# CW308T_PSoC62_MCU.net
KiCad netlist of a schematic drawn in Altium Designer
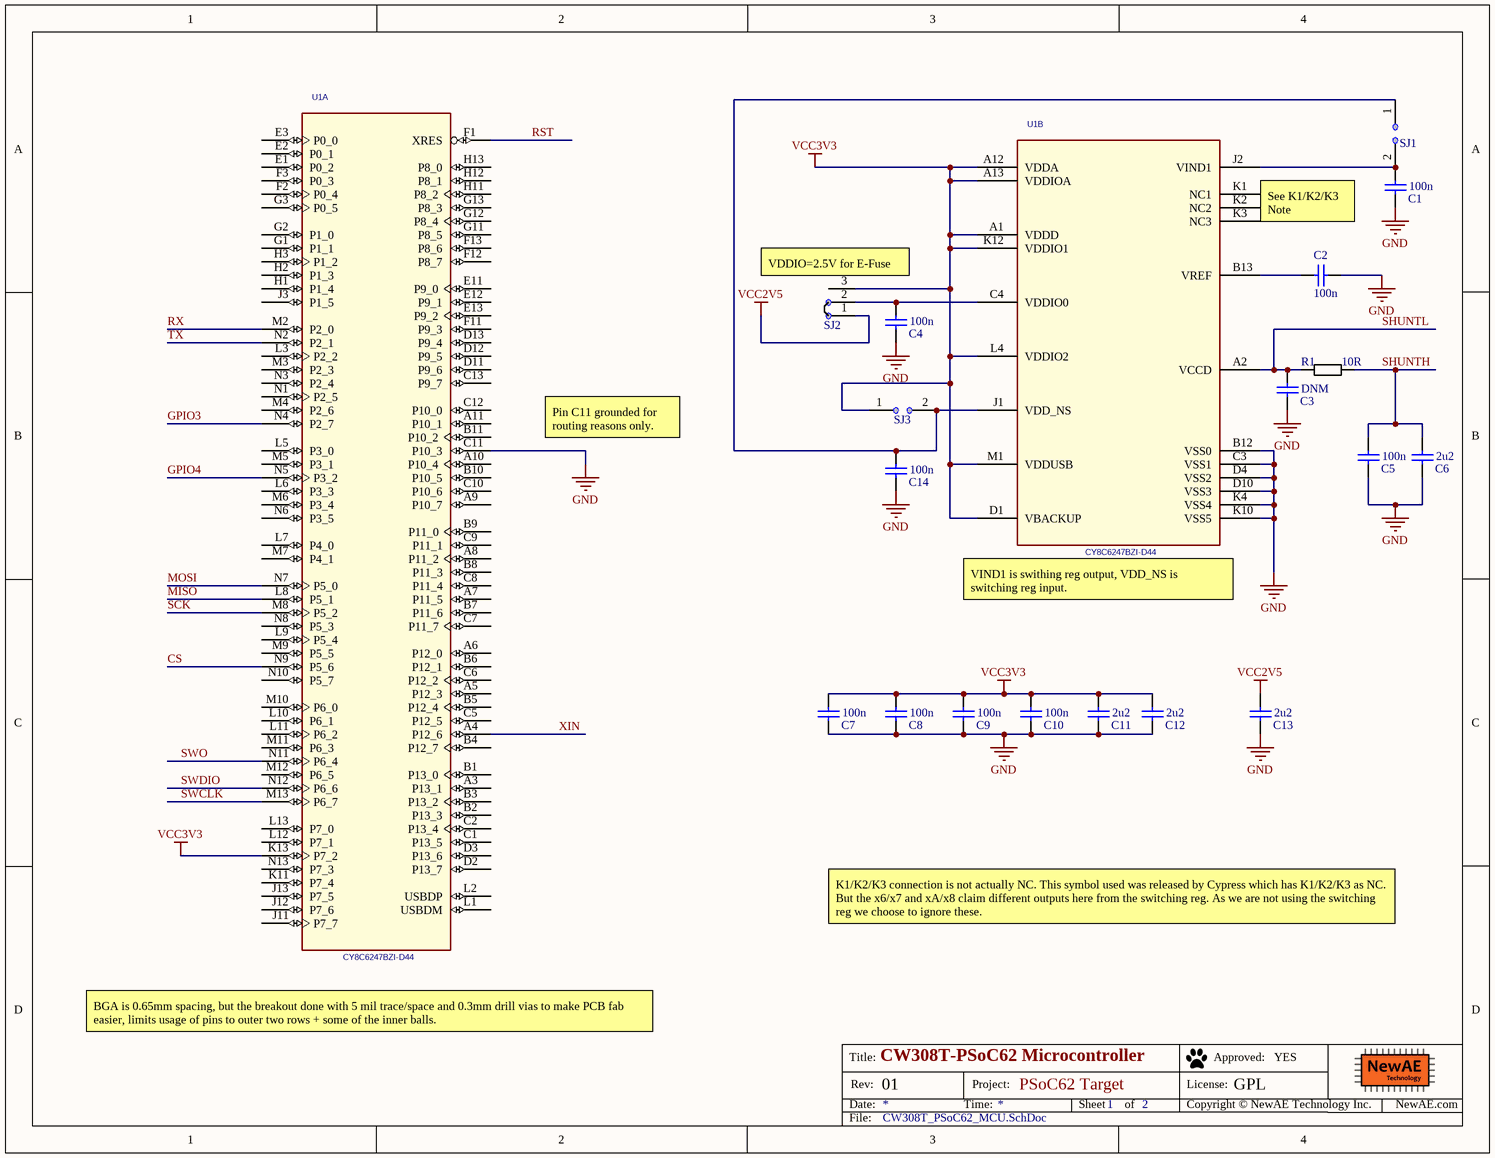
[diagram p0: CW308T_PSoC62_MCU.SchDoc]

(export (version "E")
  (design (tool "Eeschema 10.0.6"))
  (components
    (comp (ref "C1")
      (value "100n")
      (footprint "CAPC0603_M")
      (description "100n, 0603")
      (fields (field (name "PART NUMBER") "CCHIP-100n-0603"))
      (libsource (lib "NewAE_AltiumLib") (part "CAP"))
    )
    (comp (ref "C2")
      (value "100n")
      (footprint "CAPC0603_M")
      (description "100n, 0603")
      (fields (field (name "PART NUMBER") "CCHIP-100n-0603"))
      (libsource (lib "NewAE_AltiumLib") (part "CAP"))
    )
    (comp (ref "C3")
      (value "DNM")
      (footprint "CAPC0603_M")
      (description "DNM, 0603")
      (fields (field (name "PART NUMBER") "CCHIP-DNM-0603"))
      (libsource (lib "NewAE_AltiumLib") (part "CAP"))
    )
    (comp (ref "C4")
      (value "100n")
      (footprint "CAPC0603_M")
      (description "100n, 0603")
      (fields (field (name "PART NUMBER") "CCHIP-100n-0603"))
      (libsource (lib "NewAE_AltiumLib") (part "CAP"))
    )
    (comp (ref "C5")
      (value "100n")
      (footprint "CAPC0603_M")
      (description "100n, 0603")
      (fields (field (name "PART NUMBER") "CCHIP-100n-0603"))
      (libsource (lib "NewAE_AltiumLib") (part "CAP"))
    )
    (comp (ref "C6")
      (value "2u2")
      (footprint "CAPC0603_M")
      (description "2u2, 0603")
      (fields (field (name "PART NUMBER") "CCHIP-2u2-0603"))
      (libsource (lib "NewAE_AltiumLib") (part "CAP"))
    )
    (comp (ref "C7")
      (value "100n")
      (footprint "CAPC0603_M")
      (description "100n, 0603")
      (fields (field (name "PART NUMBER") "CCHIP-100n-0603"))
      (libsource (lib "NewAE_AltiumLib") (part "CAP"))
    )
    (comp (ref "C8")
      (value "100n")
      (footprint "CAPC0603_M")
      (description "100n, 0603")
      (fields (field (name "PART NUMBER") "CCHIP-100n-0603"))
      (libsource (lib "NewAE_AltiumLib") (part "CAP"))
    )
    (comp (ref "C9")
      (value "100n")
      (footprint "CAPC0603_M")
      (description "100n, 0603")
      (fields (field (name "PART NUMBER") "CCHIP-100n-0603"))
      (libsource (lib "NewAE_AltiumLib") (part "CAP"))
    )
    (comp (ref "C10")
      (value "100n")
      (footprint "CAPC0603_M")
      (description "100n, 0603")
      (fields (field (name "PART NUMBER") "CCHIP-100n-0603"))
      (libsource (lib "NewAE_AltiumLib") (part "CAP"))
    )
    (comp (ref "C11")
      (value "2u2")
      (footprint "CAPC0603_M")
      (description "2u2, 0603")
      (fields (field (name "PART NUMBER") "CCHIP-2u2-0603"))
      (libsource (lib "NewAE_AltiumLib") (part "CAP"))
    )
    (comp (ref "C12")
      (value "2u2")
      (footprint "CAPC0603_M")
      (description "2u2, 0603")
      (fields (field (name "PART NUMBER") "CCHIP-2u2-0603"))
      (libsource (lib "NewAE_AltiumLib") (part "CAP"))
    )
    (comp (ref "C13")
      (value "2u2")
      (footprint "CAPC0603_M")
      (description "2u2, 0603")
      (fields (field (name "PART NUMBER") "CCHIP-2u2-0603"))
      (libsource (lib "NewAE_AltiumLib") (part "CAP"))
    )
    (comp (ref "C14")
      (value "100n")
      (footprint "CAPC0603_M")
      (description "100n, 0603")
      (fields (field (name "PART NUMBER") "CCHIP-100n-0603"))
      (libsource (lib "NewAE_AltiumLib") (part "CAP"))
    )
    (comp (ref "R1")
      (value "10R")
      (footprint "RESC1608X55N")
      (description "10R res, 0603, 1%, 1/10W")
      (fields (field (name "PART NUMBER") "RCHIP-10R-0603") (field (name "TOLERANCE") "1%"))
      (libsource (lib "NewAE_AltiumLib") (part "RES-EU"))
    )
    (comp (ref "SJ1")
      (value "NO")
      (footprint "SJ_2S_NO")
      (description "Solder Jumper, NO")
      (fields (field (name "PART NUMBER") "SJ_2S_NO"))
      (libsource (lib "NewAE_AltiumLib") (part "SJ_2S_NO"))
    )
    (comp (ref "SJ2")
      (value "NC")
      (footprint "SJ_3S_NC12")
      (description "Solder Jumper, NC")
      (fields (field (name "PART NUMBER") "SJ_3S_12JMP"))
      (libsource (lib "NewAE_AltiumLib") (part "SJ_3S_12JMP"))
    )
    (comp (ref "SJ3")
      (value "NO")
      (footprint "SJ_2S_NO")
      (description "Solder Jumper, NO")
      (fields (field (name "PART NUMBER") "SJ_2S_NO"))
      (libsource (lib "NewAE_AltiumLib") (part "SJ_2S_NO"))
    )
    (comp (ref "U1")
      (value "CY8C6247BZI-D44")
      (footprint "BGA124C65P13X13_900X900X100")
      (description "IC DUAL CORE MCU 32B 512K 124BGA")
      (fields (field (name "PART NUMBER") "CY8C6246BZI-D04"))
      (libsource (lib "NewAE_AltiumLib") (part "CY8C6BGA124_065P"))
    )
  )
  (nets
    (net (code "1") (name "/CS") (class "Default")
      (node (ref "U1") (pin "N9") (pinfunction "P5_6_N9") (pintype "bidirectional"))
    )
    (net (code "2") (name "/GPIO3") (class "Default")
      (node (ref "U1") (pin "N4") (pinfunction "P2_7_N4") (pintype "bidirectional"))
    )
    (net (code "3") (name "/GPIO4") (class "Default")
      (node (ref "U1") (pin "N5") (pinfunction "P3_2_N5") (pintype "bidirectional"))
    )
    (net (code "4") (name "/MISO") (class "Default")
      (node (ref "U1") (pin "L8") (pinfunction "P5_1_L8") (pintype "bidirectional"))
    )
    (net (code "5") (name "/MOSI") (class "Default")
      (node (ref "U1") (pin "N7") (pinfunction "P5_0_N7") (pintype "bidirectional"))
    )
    (net (code "6") (name "/RST") (class "Default")
      (node (ref "U1") (pin "F1") (pinfunction "XRES_F1") (pintype "bidirectional"))
    )
    (net (code "7") (name "/RX") (class "Default")
      (node (ref "U1") (pin "M2") (pinfunction "P2_0_M2") (pintype "bidirectional"))
    )
    (net (code "8") (name "/SCK") (class "Default")
      (node (ref "U1") (pin "M8") (pinfunction "P5_2_M8") (pintype "bidirectional"))
    )
    (net (code "9") (name "/SHUNTH") (class "Default")
      (node (ref "C5") (pin "1") (pinfunction "1_1") (pintype "passive"))
      (node (ref "C6") (pin "1") (pinfunction "1_1") (pintype "passive"))
      (node (ref "R1") (pin "2") (pinfunction "2_2") (pintype "passive"))
    )
    (net (code "10") (name "/SHUNTL") (class "Default")
      (node (ref "C3") (pin "1") (pinfunction "1_1") (pintype "passive"))
      (node (ref "R1") (pin "1") (pinfunction "1_1") (pintype "passive"))
      (node (ref "U1") (pin "A2") (pinfunction "VCCD_A2") (pintype "power_in"))
    )
    (net (code "11") (name "/SWCLK") (class "Default")
      (node (ref "U1") (pin "M13") (pinfunction "P6_7_M13") (pintype "bidirectional"))
    )
    (net (code "12") (name "/SWDIO") (class "Default")
      (node (ref "U1") (pin "N12") (pinfunction "P6_6_N12") (pintype "bidirectional"))
    )
    (net (code "13") (name "/SWO") (class "Default")
      (node (ref "U1") (pin "N11") (pinfunction "P6_4_N11") (pintype "bidirectional"))
    )
    (net (code "14") (name "/TX") (class "Default")
      (node (ref "U1") (pin "N2") (pinfunction "P2_1_N2") (pintype "bidirectional"))
    )
    (net (code "15") (name "/XIN") (class "Default")
      (node (ref "U1") (pin "A4") (pinfunction "P12_6_A4") (pintype "bidirectional"))
    )
    (net (code "16") (name "GND") (class "Default")
      (node (ref "C1") (pin "2") (pinfunction "2_2") (pintype "passive"))
      (node (ref "C10") (pin "2") (pinfunction "2_2") (pintype "passive"))
      (node (ref "C11") (pin "2") (pinfunction "2_2") (pintype "passive"))
      (node (ref "C12") (pin "2") (pinfunction "2_2") (pintype "passive"))
      (node (ref "C13") (pin "2") (pinfunction "2_2") (pintype "passive"))
      (node (ref "C14") (pin "2") (pinfunction "2_2") (pintype "passive"))
      (node (ref "C2") (pin "2") (pinfunction "2_2") (pintype "passive"))
      (node (ref "C3") (pin "2") (pinfunction "2_2") (pintype "passive"))
      (node (ref "C4") (pin "2") (pinfunction "2_2") (pintype "passive"))
      (node (ref "C5") (pin "2") (pinfunction "2_2") (pintype "passive"))
      (node (ref "C6") (pin "2") (pinfunction "2_2") (pintype "passive"))
      (node (ref "C7") (pin "2") (pinfunction "2_2") (pintype "passive"))
      (node (ref "C8") (pin "2") (pinfunction "2_2") (pintype "passive"))
      (node (ref "C9") (pin "2") (pinfunction "2_2") (pintype "passive"))
      (node (ref "U1") (pin "B12") (pinfunction "VSS0_B12") (pintype "power_in"))
      (node (ref "U1") (pin "C11") (pinfunction "P10_3_C11") (pintype "bidirectional"))
      (node (ref "U1") (pin "C3") (pinfunction "VSS1_C3") (pintype "power_in"))
      (node (ref "U1") (pin "D10") (pinfunction "VSS3_D10") (pintype "power_in"))
      (node (ref "U1") (pin "D4") (pinfunction "VSS2_D4") (pintype "power_in"))
      (node (ref "U1") (pin "K10") (pinfunction "VSS5_K10") (pintype "power_in"))
      (node (ref "U1") (pin "K4") (pinfunction "VSS4_K4") (pintype "power_in"))
    )
    (net (code "17") (name "Net-(U1B-VDDIO0)") (class "Default")
      (node (ref "C4") (pin "1") (pinfunction "1_1") (pintype "passive"))
      (node (ref "SJ2") (pin "2") (pinfunction "2_2") (pintype "passive"))
      (node (ref "U1") (pin "C4") (pinfunction "VDDIO0_C4") (pintype "power_in"))
    )
    (net (code "18") (name "Net-(U1B-VDD_NS)") (class "Default")
      (node (ref "C14") (pin "1") (pinfunction "1_1") (pintype "passive"))
      (node (ref "SJ1") (pin "1") (pinfunction "1_1") (pintype "passive"))
      (node (ref "SJ3") (pin "2") (pinfunction "2_2") (pintype "passive"))
      (node (ref "U1") (pin "J1") (pinfunction "VDD_NS_J1") (pintype "power_in"))
    )
    (net (code "19") (name "Net-(U1B-VIND1)") (class "Default")
      (node (ref "C1") (pin "1") (pinfunction "1_1") (pintype "passive"))
      (node (ref "SJ1") (pin "2") (pinfunction "2_2") (pintype "passive"))
      (node (ref "U1") (pin "J2") (pinfunction "VIND1_J2") (pintype "power_in"))
    )
    (net (code "20") (name "Net-(U1B-VREF)") (class "Default")
      (node (ref "C2") (pin "1") (pinfunction "1_1") (pintype "passive"))
      (node (ref "U1") (pin "B13") (pinfunction "VREF_B13") (pintype "power_in"))
    )
    (net (code "21") (name "VCC2V5") (class "Default")
      (node (ref "C13") (pin "1") (pinfunction "1_1") (pintype "passive"))
      (node (ref "SJ2") (pin "1") (pinfunction "1_1") (pintype "passive"))
    )
    (net (code "22") (name "VCC3V3") (class "Default")
      (node (ref "C10") (pin "1") (pinfunction "1_1") (pintype "passive"))
      (node (ref "C11") (pin "1") (pinfunction "1_1") (pintype "passive"))
      (node (ref "C12") (pin "1") (pinfunction "1_1") (pintype "passive"))
      (node (ref "C7") (pin "1") (pinfunction "1_1") (pintype "passive"))
      (node (ref "C8") (pin "1") (pinfunction "1_1") (pintype "passive"))
      (node (ref "C9") (pin "1") (pinfunction "1_1") (pintype "passive"))
      (node (ref "SJ2") (pin "3") (pinfunction "3_3") (pintype "passive"))
      (node (ref "SJ3") (pin "1") (pinfunction "1_1") (pintype "passive"))
      (node (ref "U1") (pin "A1") (pinfunction "VDDD_A1") (pintype "power_in"))
      (node (ref "U1") (pin "A12") (pinfunction "VDDA_A12") (pintype "power_in"))
      (node (ref "U1") (pin "A13") (pinfunction "VDDIOA_A13") (pintype "power_in"))
      (node (ref "U1") (pin "D1") (pinfunction "VBACKUP_D1") (pintype "power_in"))
      (node (ref "U1") (pin "K12") (pinfunction "VDDIO1_K12") (pintype "power_in"))
      (node (ref "U1") (pin "K13") (pinfunction "P7_2_K13") (pintype "bidirectional"))
      (node (ref "U1") (pin "L4") (pinfunction "VDDIO2_L4") (pintype "power_in"))
      (node (ref "U1") (pin "M1") (pinfunction "VDDUSB_M1") (pintype "power_in"))
    )
    (net (code "23") (name "unconnected-(U1A-P0_0-PadE3)") (class "Default")
      (node (ref "U1") (pin "E3") (pinfunction "P0_0_E3") (pintype "bidirectional"))
    )
    (net (code "24") (name "unconnected-(U1A-P0_1-PadE2)") (class "Default")
      (node (ref "U1") (pin "E2") (pinfunction "P0_1_E2") (pintype "bidirectional"))
    )
    (net (code "25") (name "unconnected-(U1A-P0_2-PadE1)") (class "Default")
      (node (ref "U1") (pin "E1") (pinfunction "P0_2_E1") (pintype "bidirectional"))
    )
    (net (code "26") (name "unconnected-(U1A-P0_3-PadF3)") (class "Default")
      (node (ref "U1") (pin "F3") (pinfunction "P0_3_F3") (pintype "bidirectional"))
    )
    (net (code "27") (name "unconnected-(U1A-P0_4-PadF2)") (class "Default")
      (node (ref "U1") (pin "F2") (pinfunction "P0_4_F2") (pintype "bidirectional"))
    )
    (net (code "28") (name "unconnected-(U1A-P0_5-PadG3)") (class "Default")
      (node (ref "U1") (pin "G3") (pinfunction "P0_5_G3") (pintype "bidirectional"))
    )
    (net (code "29") (name "unconnected-(U1A-P1_0-PadG2)") (class "Default")
      (node (ref "U1") (pin "G2") (pinfunction "P1_0_G2") (pintype "bidirectional"))
    )
    (net (code "30") (name "unconnected-(U1A-P1_1-PadG1)") (class "Default")
      (node (ref "U1") (pin "G1") (pinfunction "P1_1_G1") (pintype "bidirectional"))
    )
    (net (code "31") (name "unconnected-(U1A-P1_2-PadH3)") (class "Default")
      (node (ref "U1") (pin "H3") (pinfunction "P1_2_H3") (pintype "bidirectional"))
    )
    (net (code "32") (name "unconnected-(U1A-P1_3-PadH2)") (class "Default")
      (node (ref "U1") (pin "H2") (pinfunction "P1_3_H2") (pintype "bidirectional"))
    )
    (net (code "33") (name "unconnected-(U1A-P1_4-PadH1)") (class "Default")
      (node (ref "U1") (pin "H1") (pinfunction "P1_4_H1") (pintype "bidirectional"))
    )
    (net (code "34") (name "unconnected-(U1A-P1_5-PadJ3)") (class "Default")
      (node (ref "U1") (pin "J3") (pinfunction "P1_5_J3") (pintype "bidirectional"))
    )
    (net (code "35") (name "unconnected-(U1A-P2_2-PadL3)") (class "Default")
      (node (ref "U1") (pin "L3") (pinfunction "P2_2_L3") (pintype "bidirectional"))
    )
    (net (code "36") (name "unconnected-(U1A-P2_3-PadM3)") (class "Default")
      (node (ref "U1") (pin "M3") (pinfunction "P2_3_M3") (pintype "bidirectional"))
    )
    (net (code "37") (name "unconnected-(U1A-P2_4-PadN3)") (class "Default")
      (node (ref "U1") (pin "N3") (pinfunction "P2_4_N3") (pintype "bidirectional"))
    )
    (net (code "38") (name "unconnected-(U1A-P2_5-PadN1)") (class "Default")
      (node (ref "U1") (pin "N1") (pinfunction "P2_5_N1") (pintype "bidirectional"))
    )
    (net (code "39") (name "unconnected-(U1A-P2_6-PadM4)") (class "Default")
      (node (ref "U1") (pin "M4") (pinfunction "P2_6_M4") (pintype "bidirectional"))
    )
    (net (code "40") (name "unconnected-(U1A-P3_0-PadL5)") (class "Default")
      (node (ref "U1") (pin "L5") (pinfunction "P3_0_L5") (pintype "bidirectional"))
    )
    (net (code "41") (name "unconnected-(U1A-P3_1-PadM5)") (class "Default")
      (node (ref "U1") (pin "M5") (pinfunction "P3_1_M5") (pintype "bidirectional"))
    )
    (net (code "42") (name "unconnected-(U1A-P3_3-PadL6)") (class "Default")
      (node (ref "U1") (pin "L6") (pinfunction "P3_3_L6") (pintype "bidirectional"))
    )
    (net (code "43") (name "unconnected-(U1A-P3_4-PadM6)") (class "Default")
      (node (ref "U1") (pin "M6") (pinfunction "P3_4_M6") (pintype "bidirectional"))
    )
    (net (code "44") (name "unconnected-(U1A-P3_5-PadN6)") (class "Default")
      (node (ref "U1") (pin "N6") (pinfunction "P3_5_N6") (pintype "bidirectional"))
    )
    (net (code "45") (name "unconnected-(U1A-P4_0-PadL7)") (class "Default")
      (node (ref "U1") (pin "L7") (pinfunction "P4_0_L7") (pintype "bidirectional"))
    )
    (net (code "46") (name "unconnected-(U1A-P4_1-PadM7)") (class "Default")
      (node (ref "U1") (pin "M7") (pinfunction "P4_1_M7") (pintype "bidirectional"))
    )
    (net (code "47") (name "unconnected-(U1A-P5_3-PadN8)") (class "Default")
      (node (ref "U1") (pin "N8") (pinfunction "P5_3_N8") (pintype "bidirectional"))
    )
    (net (code "48") (name "unconnected-(U1A-P5_4-PadL9)") (class "Default")
      (node (ref "U1") (pin "L9") (pinfunction "P5_4_L9") (pintype "bidirectional"))
    )
    (net (code "49") (name "unconnected-(U1A-P5_5-PadM9)") (class "Default")
      (node (ref "U1") (pin "M9") (pinfunction "P5_5_M9") (pintype "bidirectional"))
    )
    (net (code "50") (name "unconnected-(U1A-P5_7-PadN10)") (class "Default")
      (node (ref "U1") (pin "N10") (pinfunction "P5_7_N10") (pintype "bidirectional"))
    )
    (net (code "51") (name "unconnected-(U1A-P6_0-PadM10)") (class "Default")
      (node (ref "U1") (pin "M10") (pinfunction "P6_0_M10") (pintype "bidirectional"))
    )
    (net (code "52") (name "unconnected-(U1A-P6_1-PadL10)") (class "Default")
      (node (ref "U1") (pin "L10") (pinfunction "P6_1_L10") (pintype "bidirectional"))
    )
    (net (code "53") (name "unconnected-(U1A-P6_2-PadL11)") (class "Default")
      (node (ref "U1") (pin "L11") (pinfunction "P6_2_L11") (pintype "bidirectional"))
    )
    (net (code "54") (name "unconnected-(U1A-P6_3-PadM11)") (class "Default")
      (node (ref "U1") (pin "M11") (pinfunction "P6_3_M11") (pintype "bidirectional"))
    )
    (net (code "55") (name "unconnected-(U1A-P6_5-PadM12)") (class "Default")
      (node (ref "U1") (pin "M12") (pinfunction "P6_5_M12") (pintype "bidirectional"))
    )
    (net (code "56") (name "unconnected-(U1A-P7_0-PadL13)") (class "Default")
      (node (ref "U1") (pin "L13") (pinfunction "P7_0_L13") (pintype "bidirectional"))
    )
    (net (code "57") (name "unconnected-(U1A-P7_1-PadL12)") (class "Default")
      (node (ref "U1") (pin "L12") (pinfunction "P7_1_L12") (pintype "bidirectional"))
    )
    (net (code "58") (name "unconnected-(U1A-P7_3-PadN13)") (class "Default")
      (node (ref "U1") (pin "N13") (pinfunction "P7_3_N13") (pintype "bidirectional"))
    )
    (net (code "59") (name "unconnected-(U1A-P7_4-PadK11)") (class "Default")
      (node (ref "U1") (pin "K11") (pinfunction "P7_4_K11") (pintype "bidirectional"))
    )
    (net (code "60") (name "unconnected-(U1A-P7_5-PadJ13)") (class "Default")
      (node (ref "U1") (pin "J13") (pinfunction "P7_5_J13") (pintype "bidirectional"))
    )
    (net (code "61") (name "unconnected-(U1A-P7_6-PadJ12)") (class "Default")
      (node (ref "U1") (pin "J12") (pinfunction "P7_6_J12") (pintype "bidirectional"))
    )
    (net (code "62") (name "unconnected-(U1A-P7_7-PadJ11)") (class "Default")
      (node (ref "U1") (pin "J11") (pinfunction "P7_7_J11") (pintype "bidirectional"))
    )
    (net (code "63") (name "unconnected-(U1A-P8_0-PadH13)") (class "Default")
      (node (ref "U1") (pin "H13") (pinfunction "P8_0_H13") (pintype "bidirectional"))
    )
    (net (code "64") (name "unconnected-(U1A-P8_1-PadH12)") (class "Default")
      (node (ref "U1") (pin "H12") (pinfunction "P8_1_H12") (pintype "bidirectional"))
    )
    (net (code "65") (name "unconnected-(U1A-P8_2-PadH11)") (class "Default")
      (node (ref "U1") (pin "H11") (pinfunction "P8_2_H11") (pintype "bidirectional"))
    )
    (net (code "66") (name "unconnected-(U1A-P8_3-PadG13)") (class "Default")
      (node (ref "U1") (pin "G13") (pinfunction "P8_3_G13") (pintype "bidirectional"))
    )
    (net (code "67") (name "unconnected-(U1A-P8_4-PadG12)") (class "Default")
      (node (ref "U1") (pin "G12") (pinfunction "P8_4_G12") (pintype "bidirectional"))
    )
    (net (code "68") (name "unconnected-(U1A-P8_5-PadG11)") (class "Default")
      (node (ref "U1") (pin "G11") (pinfunction "P8_5_G11") (pintype "bidirectional"))
    )
    (net (code "69") (name "unconnected-(U1A-P8_6-PadF13)") (class "Default")
      (node (ref "U1") (pin "F13") (pinfunction "P8_6_F13") (pintype "bidirectional"))
    )
    (net (code "70") (name "unconnected-(U1A-P8_7-PadF12)") (class "Default")
      (node (ref "U1") (pin "F12") (pinfunction "P8_7_F12") (pintype "bidirectional"))
    )
    (net (code "71") (name "unconnected-(U1A-P9_0-PadE11)") (class "Default")
      (node (ref "U1") (pin "E11") (pinfunction "P9_0_E11") (pintype "bidirectional"))
    )
    (net (code "72") (name "unconnected-(U1A-P9_1-PadE12)") (class "Default")
      (node (ref "U1") (pin "E12") (pinfunction "P9_1_E12") (pintype "bidirectional"))
    )
    (net (code "73") (name "unconnected-(U1A-P9_2-PadE13)") (class "Default")
      (node (ref "U1") (pin "E13") (pinfunction "P9_2_E13") (pintype "bidirectional"))
    )
    (net (code "74") (name "unconnected-(U1A-P9_3-PadF11)") (class "Default")
      (node (ref "U1") (pin "F11") (pinfunction "P9_3_F11") (pintype "bidirectional"))
    )
    (net (code "75") (name "unconnected-(U1A-P9_4-PadD13)") (class "Default")
      (node (ref "U1") (pin "D13") (pinfunction "P9_4_D13") (pintype "bidirectional"))
    )
    (net (code "76") (name "unconnected-(U1A-P9_5-PadD12)") (class "Default")
      (node (ref "U1") (pin "D12") (pinfunction "P9_5_D12") (pintype "bidirectional"))
    )
    (net (code "77") (name "unconnected-(U1A-P9_6-PadD11)") (class "Default")
      (node (ref "U1") (pin "D11") (pinfunction "P9_6_D11") (pintype "bidirectional"))
    )
    (net (code "78") (name "unconnected-(U1A-P9_7-PadC13)") (class "Default")
      (node (ref "U1") (pin "C13") (pinfunction "P9_7_C13") (pintype "bidirectional"))
    )
    (net (code "79") (name "unconnected-(U1A-P10_0-PadC12)") (class "Default")
      (node (ref "U1") (pin "C12") (pinfunction "P10_0_C12") (pintype "bidirectional"))
    )
    (net (code "80") (name "unconnected-(U1A-P10_1-PadA11)") (class "Default")
      (node (ref "U1") (pin "A11") (pinfunction "P10_1_A11") (pintype "bidirectional"))
    )
    (net (code "81") (name "unconnected-(U1A-P10_2-PadB11)") (class "Default")
      (node (ref "U1") (pin "B11") (pinfunction "P10_2_B11") (pintype "bidirectional"))
    )
    (net (code "82") (name "unconnected-(U1A-P10_4-PadA10)") (class "Default")
      (node (ref "U1") (pin "A10") (pinfunction "P10_4_A10") (pintype "bidirectional"))
    )
    (net (code "83") (name "unconnected-(U1A-P10_5-PadB10)") (class "Default")
      (node (ref "U1") (pin "B10") (pinfunction "P10_5_B10") (pintype "bidirectional"))
    )
    (net (code "84") (name "unconnected-(U1A-P10_6-PadC10)") (class "Default")
      (node (ref "U1") (pin "C10") (pinfunction "P10_6_C10") (pintype "bidirectional"))
    )
    (net (code "85") (name "unconnected-(U1A-P10_7-PadA9)") (class "Default")
      (node (ref "U1") (pin "A9") (pinfunction "P10_7_A9") (pintype "bidirectional"))
    )
    (net (code "86") (name "unconnected-(U1A-P11_0-PadB9)") (class "Default")
      (node (ref "U1") (pin "B9") (pinfunction "P11_0_B9") (pintype "bidirectional"))
    )
    (net (code "87") (name "unconnected-(U1A-P11_1-PadC9)") (class "Default")
      (node (ref "U1") (pin "C9") (pinfunction "P11_1_C9") (pintype "bidirectional"))
    )
    (net (code "88") (name "unconnected-(U1A-P11_2-PadA8)") (class "Default")
      (node (ref "U1") (pin "A8") (pinfunction "P11_2_A8") (pintype "bidirectional"))
    )
    (net (code "89") (name "unconnected-(U1A-P11_3-PadB8)") (class "Default")
      (node (ref "U1") (pin "B8") (pinfunction "P11_3_B8") (pintype "bidirectional"))
    )
    (net (code "90") (name "unconnected-(U1A-P11_4-PadC8)") (class "Default")
      (node (ref "U1") (pin "C8") (pinfunction "P11_4_C8") (pintype "bidirectional"))
    )
    (net (code "91") (name "unconnected-(U1A-P11_5-PadA7)") (class "Default")
      (node (ref "U1") (pin "A7") (pinfunction "P11_5_A7") (pintype "bidirectional"))
    )
    (net (code "92") (name "unconnected-(U1A-P11_6-PadB7)") (class "Default")
      (node (ref "U1") (pin "B7") (pinfunction "P11_6_B7") (pintype "bidirectional"))
    )
    (net (code "93") (name "unconnected-(U1A-P11_7-PadC7)") (class "Default")
      (node (ref "U1") (pin "C7") (pinfunction "P11_7_C7") (pintype "bidirectional"))
    )
    (net (code "94") (name "unconnected-(U1A-P12_0-PadA6)") (class "Default")
      (node (ref "U1") (pin "A6") (pinfunction "P12_0_A6") (pintype "bidirectional"))
    )
    (net (code "95") (name "unconnected-(U1A-P12_1-PadB6)") (class "Default")
      (node (ref "U1") (pin "B6") (pinfunction "P12_1_B6") (pintype "bidirectional"))
    )
    (net (code "96") (name "unconnected-(U1A-P12_2-PadC6)") (class "Default")
      (node (ref "U1") (pin "C6") (pinfunction "P12_2_C6") (pintype "bidirectional"))
    )
    (net (code "97") (name "unconnected-(U1A-P12_3-PadA5)") (class "Default")
      (node (ref "U1") (pin "A5") (pinfunction "P12_3_A5") (pintype "bidirectional"))
    )
    (net (code "98") (name "unconnected-(U1A-P12_4-PadB5)") (class "Default")
      (node (ref "U1") (pin "B5") (pinfunction "P12_4_B5") (pintype "bidirectional"))
    )
    (net (code "99") (name "unconnected-(U1A-P12_5-PadC5)") (class "Default")
      (node (ref "U1") (pin "C5") (pinfunction "P12_5_C5") (pintype "bidirectional"))
    )
    (net (code "100") (name "unconnected-(U1A-P12_7-PadB4)") (class "Default")
      (node (ref "U1") (pin "B4") (pinfunction "P12_7_B4") (pintype "bidirectional"))
    )
    (net (code "101") (name "unconnected-(U1A-P13_0-PadB1)") (class "Default")
      (node (ref "U1") (pin "B1") (pinfunction "P13_0_B1") (pintype "bidirectional"))
    )
    (net (code "102") (name "unconnected-(U1A-P13_1-PadA3)") (class "Default")
      (node (ref "U1") (pin "A3") (pinfunction "P13_1_A3") (pintype "bidirectional"))
    )
    (net (code "103") (name "unconnected-(U1A-P13_2-PadB3)") (class "Default")
      (node (ref "U1") (pin "B3") (pinfunction "P13_2_B3") (pintype "bidirectional"))
    )
    (net (code "104") (name "unconnected-(U1A-P13_3-PadB2)") (class "Default")
      (node (ref "U1") (pin "B2") (pinfunction "P13_3_B2") (pintype "bidirectional"))
    )
    (net (code "105") (name "unconnected-(U1A-P13_4-PadC2)") (class "Default")
      (node (ref "U1") (pin "C2") (pinfunction "P13_4_C2") (pintype "bidirectional"))
    )
    (net (code "106") (name "unconnected-(U1A-P13_5-PadC1)") (class "Default")
      (node (ref "U1") (pin "C1") (pinfunction "P13_5_C1") (pintype "bidirectional"))
    )
    (net (code "107") (name "unconnected-(U1A-P13_6-PadD3)") (class "Default")
      (node (ref "U1") (pin "D3") (pinfunction "P13_6_D3") (pintype "bidirectional"))
    )
    (net (code "108") (name "unconnected-(U1A-P13_7-PadD2)") (class "Default")
      (node (ref "U1") (pin "D2") (pinfunction "P13_7_D2") (pintype "bidirectional"))
    )
    (net (code "109") (name "unconnected-(U1A-USBDM-PadL1)") (class "Default")
      (node (ref "U1") (pin "L1") (pinfunction "USBDM_L1") (pintype "bidirectional"))
    )
    (net (code "110") (name "unconnected-(U1A-USBDP-PadL2)") (class "Default")
      (node (ref "U1") (pin "L2") (pinfunction "USBDP_L2") (pintype "bidirectional"))
    )
    (net (code "111") (name "unconnected-(U1B-NC1-PadK1)") (class "Default")
      (node (ref "U1") (pin "K1") (pinfunction "NC1_K1") (pintype "passive"))
    )
    (net (code "112") (name "unconnected-(U1B-NC2-PadK2)") (class "Default")
      (node (ref "U1") (pin "K2") (pinfunction "NC2_K2") (pintype "passive"))
    )
    (net (code "113") (name "unconnected-(U1B-NC3-PadK3)") (class "Default")
      (node (ref "U1") (pin "K3") (pinfunction "NC3_K3") (pintype "passive"))
    )
  )
)
